# Audio_Amplifier.net
KiCad netlist of a schematic drawn in Altium Designer
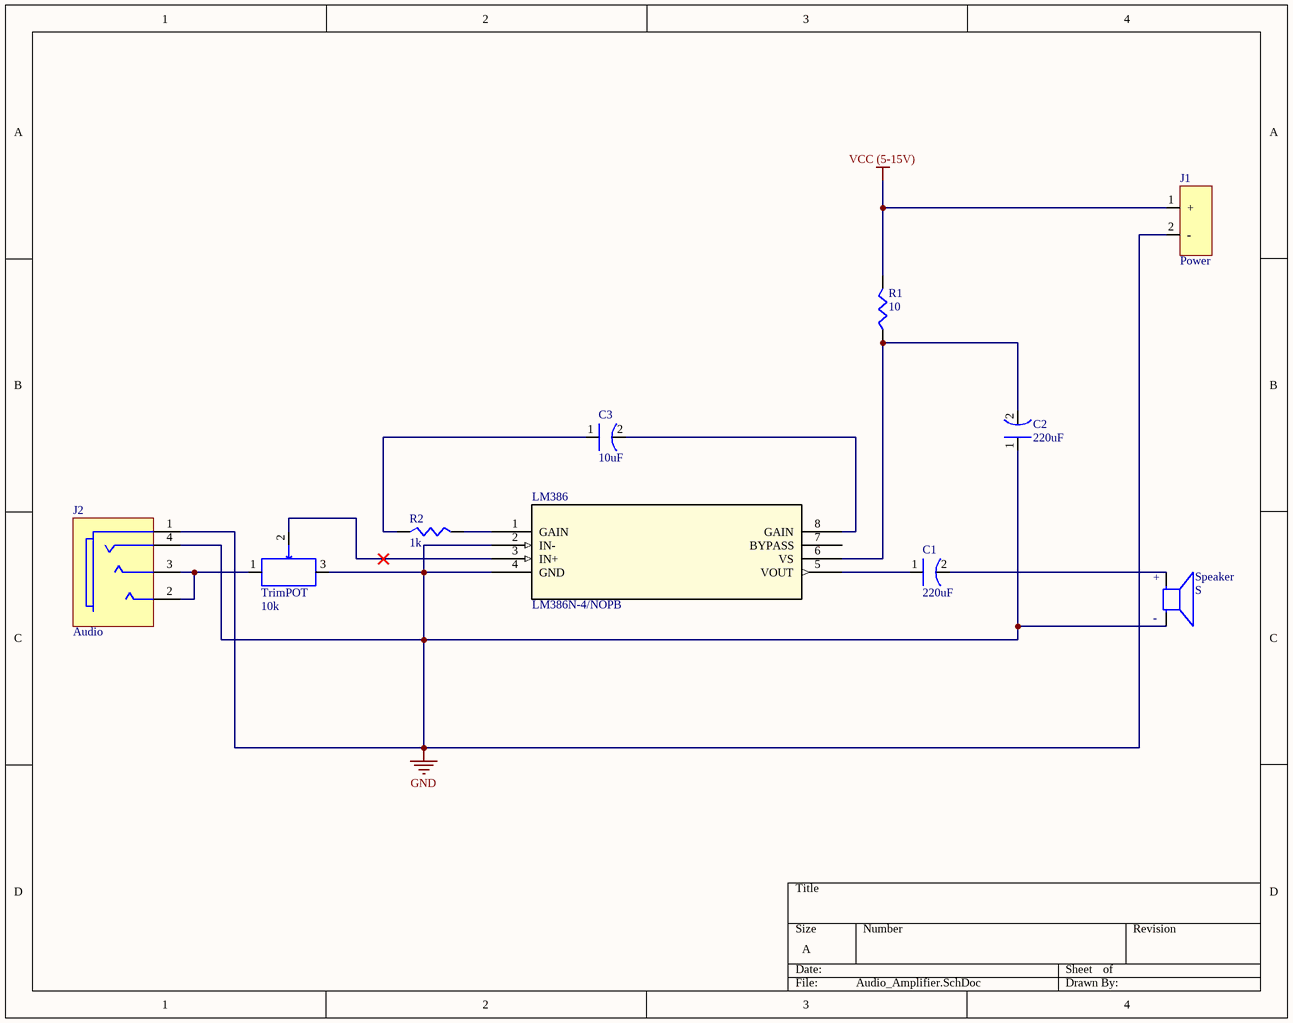
[diagram p0: Audio_Amplifier.SchDoc]

(export (version "E")
  (design (tool "Eeschema 10.0.6"))
  (components
    (comp (ref "C1")
      (value "220uF")
      (footprint "CAP_YX_6P3X11_RUB")
      (description "CAP ALUM 220UF 20% 25V RADIAL TH")
      (fields
        (field (name "MANUFACTURER") "Rubycon")
        (field (name "MANUFACTURER PART NUMBER") "25YXJ220M6.3X11")
      )
      (libsource (lib "Audio_Amplifier_Schlib") (part "25YXJ220M6.3X11"))
    )
    (comp (ref "C2")
      (value "220uF")
      (footprint "CAP_YX_6P3X11_RUB")
      (description "CAP ALUM 220UF 20% 25V RADIAL TH")
      (fields
        (field (name "MANUFACTURER") "Rubycon")
        (field (name "MANUFACTURER PART NUMBER") "25YXJ220M6.3X11")
      )
      (libsource (lib "Audio_Amplifier_Schlib") (part "25YXJ220M6.3X11"))
    )
    (comp (ref "C3")
      (value "10uF")
      (footprint "CAP_YX_5X11_RUB")
      (description "CAP ALUM 10UF 20% 50V RADIAL TH")
      (fields
        (field (name "MANUFACTURER") "Rubycon")
        (field (name "MANUFACTURER PART NUMBER") "50YXJ10M5X11")
      )
      (libsource (lib "Audio_Amplifier_Schlib") (part "50YXJ10M5X11"))
    )
    (comp (ref "J1")
      (value "Power")
      (footprint "TE_2314870-2")
      (description "2P,2MM,BB,REC,SRVT,2.0,0.76AU,TU")
      (fields
        (field (name "MANUFACTURER") "TE Connectivity / AMP")
        (field (name "MANUFACTURER PART NUMBER") "2314870-2")
      )
      (libsource (lib "Audio_Amplifier_Schlib") (part "2314870-2"))
    )
    (comp (ref "J2")
      (value "Audio")
      (footprint "SAMESKY_SJ2-3574A-SMT-TR")
      (description "AUDIO JACK, 3.5 MM, RT, 4 CONDUC")
      (fields
        (field (name "MANUFACTURER") "CUI")
        (field (name "OCTOPART") "https://octopart.com/sj2-3574a-smt-tr-cui-77838840")
      )
      (libsource (lib "Audio_Amplifier_Schlib") (part "SJ2-3574A-SMT-TR"))
    )
    (comp (ref "LM386")
      (value "LM386N-4/NOPB")
      (footprint "N08E_TEX")
      (description "IC AMP CLASS AB MONO 1W 8DIP")
      (fields (field (name "MANUFACTURER") "Texas Instruments"))
      (libsource (lib "Audio_Amplifier_Schlib") (part "LM386N-4/NOPB"))
    )
    (comp (ref "R1")
      (value "10")
      (footprint "RES_OY_OHM")
      (description "RES 10 OHM 10% 2W AXIAL")
      (fields (field (name "MANUFACTURER") "Ohmite") (field (name "MANUFACTURER PART NUMBER") "OY100KE"))
      (libsource (lib "Audio_Amplifier_Schlib") (part "OY100KE"))
    )
    (comp (ref "R2")
      (value "1k")
      (footprint "STA_CF14_STP")
      (description "RES 1K OHM 5% 1/4W AXIAL")
      (fields
        (field (name "MANUFACTURER") "Stackpole Electronics")
        (field (name "MANUFACTURER PART NUMBER") "CF14JT1K00")
      )
      (libsource (lib "Audio_Amplifier_Schlib") (part "CF14JT1K00"))
    )
    (comp (ref "Speaker")
      (value "S")
      (footprint "SPKR_AST-03208MR-R")
      (description "SPEAKER 8OHM 100MW TOP PORT 82DB")
      (fields
        (field (name "MANUFACTURER") "PUI Audio")
        (field (name "MANUFACTURER PART NUMBER") "AST-03208MR-R")
      )
      (libsource (lib "Audio_Amplifier_Schlib") (part "AST-03208MR-R"))
    )
    (comp (ref "TrimPOT")
      (value "10k")
      (footprint "TRIM_3362P-1-103LF")
      (description "TRIMMER 10K OHM 0.5W PC PIN TOP")
      (fields
        (field (name "MANUFACTURER") "Bourns")
        (field (name "MANUFACTURER PART NUMBER") "3362P-1-103LF")
      )
      (libsource (lib "Audio_Amplifier_Schlib") (part "3362P-1-103LF"))
    )
  )
  (nets
    (net (code "1") (name "GND") (class "Default")
      (node (ref "C2") (pin "1") (pinfunction "1_1") (pintype "passive"))
      (node (ref "J1") (pin "2") (pinfunction "-_2") (pintype "passive"))
      (node (ref "J2") (pin "1") (pinfunction "sleeve_1") (pintype "passive"))
      (node (ref "J2") (pin "4") (pinfunction "ring_2_4") (pintype "passive"))
      (node (ref "LM386") (pin "2") (pinfunction "IN-_2") (pintype "input"))
      (node (ref "LM386") (pin "4") (pinfunction "GND_4") (pintype "power_in"))
      (node (ref "Speaker") (pin "N") (pinfunction "NEG_N") (pintype "passive"))
      (node (ref "TrimPOT") (pin "3") (pintype "passive"))
    )
    (net (code "2") (name "Net-(C3-Pad1)") (class "Default")
      (node (ref "C3") (pin "1") (pinfunction "1_1") (pintype "passive"))
      (node (ref "R2") (pin "1") (pinfunction "1_1") (pintype "passive"))
    )
    (net (code "3") (name "Net-(C3-Pad2)") (class "Default")
      (node (ref "C3") (pin "2") (pinfunction "2_2") (pintype "passive"))
      (node (ref "LM386") (pin "8") (pinfunction "GAIN_8") (pintype "passive"))
    )
    (net (code "4") (name "Net-(J2-ring_1)") (class "Default")
      (node (ref "J2") (pin "2") (pinfunction "tip_2") (pintype "passive"))
      (node (ref "J2") (pin "3") (pinfunction "ring_1_3") (pintype "passive"))
      (node (ref "TrimPOT") (pin "1") (pintype "passive"))
    )
    (net (code "5") (name "Net-(LM386-GAIN-Pad1)") (class "Default")
      (node (ref "LM386") (pin "1") (pinfunction "GAIN_1") (pintype "passive"))
      (node (ref "R2") (pin "2") (pinfunction "2_2") (pintype "passive"))
    )
    (net (code "6") (name "Net-(LM386-IN+)") (class "Default")
      (node (ref "LM386") (pin "3") (pinfunction "IN+_3") (pintype "input"))
      (node (ref "TrimPOT") (pin "2") (pintype "passive"))
    )
    (net (code "7") (name "Net-(LM386-VOUT)") (class "Default")
      (node (ref "C1") (pin "1") (pinfunction "1_1") (pintype "passive"))
      (node (ref "LM386") (pin "5") (pinfunction "VOUT_5") (pintype "output"))
    )
    (net (code "8") (name "Net-(LM386-VS)") (class "Default")
      (node (ref "C2") (pin "2") (pinfunction "2_2") (pintype "passive"))
      (node (ref "LM386") (pin "6") (pinfunction "VS_6") (pintype "power_in"))
      (node (ref "R1") (pin "1") (pinfunction "1_1") (pintype "passive"))
    )
    (net (code "9") (name "Net-(Speaker-POS)") (class "Default")
      (node (ref "C1") (pin "2") (pinfunction "2_2") (pintype "passive"))
      (node (ref "Speaker") (pin "P") (pinfunction "POS_P") (pintype "passive"))
    )
    (net (code "10") (name "VCC (5-15V)") (class "Default")
      (node (ref "J1") (pin "1") (pinfunction "+_1") (pintype "passive"))
      (node (ref "R1") (pin "2") (pinfunction "2_2") (pintype "passive"))
    )
    (net (code "11") (name "unconnected-(LM386-BYPASS-Pad7)") (class "Default")
      (node (ref "LM386") (pin "7") (pinfunction "BYPASS_7") (pintype "passive"))
    )
  )
)
